# Gastroscopy-Controller_USB.net
KiCad netlist of a schematic drawn in Altium Designer
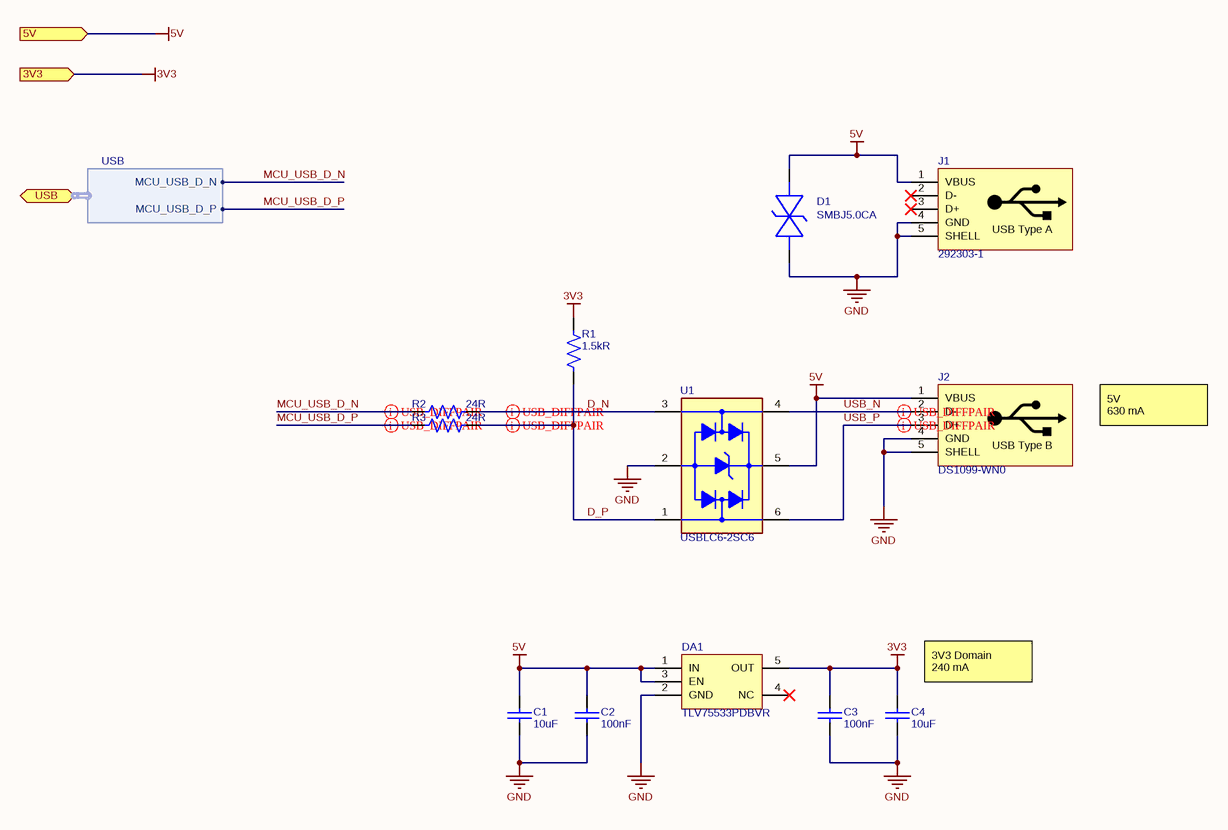
[diagram p0: Gastroscopy-Controller_USB.SchDoc]

(export (version "E")
  (design (tool "Eeschema 10.0.6"))
  (components
    (comp (ref "C1")
      (value "10uF")
      (footprint "CAP_0805")
      (description "CAP CER 10UF 16V X7R 0805")
      (fields (field (name "TOLERANCE") "10%") (field (name "VOLTAGE") "16V"))
      (libsource (lib "Gastroscopy-Controller") (part "CL21B106KOQNNNE"))
    )
    (comp (ref "C2")
      (value "100nF")
      (footprint "CAP_0603")
      (description "CAP CER 0.1UF 50V X7R 0603")
      (fields (field (name "TOLERANCE") "10%"))
      (libsource (lib "Gastroscopy-Controller") (part "CL10B104KB8NNNL"))
    )
    (comp (ref "C3")
      (value "100nF")
      (footprint "CAP_0603")
      (description "CAP CER 0.1UF 50V X7R 0603")
      (fields (field (name "TOLERANCE") "10%"))
      (libsource (lib "Gastroscopy-Controller") (part "CL10B104KB8NNNL"))
    )
    (comp (ref "C4")
      (value "10uF")
      (footprint "CAP_0805")
      (description "CAP CER 10UF 16V X7R 0805")
      (fields (field (name "TOLERANCE") "10%") (field (name "VOLTAGE") "16V"))
      (libsource (lib "Gastroscopy-Controller") (part "CL21B106KOQNNNE"))
    )
    (comp (ref "D1")
      (value "SMBJ5.0CA")
      (footprint "SMB-BIDIR")
      (description "TVS DIODE 5VWM 9.2VC SMB")
      (libsource (lib "Gastroscopy-Controller") (part "SMBJ5.0CA"))
    )
    (comp (ref "DA1")
      (value "TLV75533PDBVR")
      (footprint "SOT-23-5")
      (description "IC REG LINEAR 3.3V 500MA SOT23-5")
      (libsource (lib "Gastroscopy-Controller") (part "TLV75533PDBVR"))
    )
    (comp (ref "J1")
      (value "292303-1")
      (footprint "292303-1")
      (description "Conn USB 2.0 Type A RCP 4 POS 2mm/2.5mm Solder RA Thru-Hole 4 Terminal 1 Port Box/Tube")
      (libsource (lib "Gastroscopy-Controller") (part "292303-1"))
    )
    (comp (ref "J2")
      (value "DS1099-WN0")
      (footprint "DS1099-WN0")
      (description "CONN TYPE B SKT HORIZONTAL TH")
      (libsource (lib "Industrial-Controller") (part "DS1099-WN0"))
    )
    (comp (ref "R1")
      (value "1.5kR")
      (footprint "RES_0603")
      (description "RES 1.5K OHM 1% 1/10W 0603")
      (fields (field (name "TOLERANCE") "1%"))
      (libsource (lib "Gastroscopy-Controller") (part "RC0603FR-071K5L"))
    )
    (comp (ref "R2")
      (value "24R")
      (footprint "RES_0603")
      (description "RES 24 OHM 1% 1/10W 0603")
      (fields (field (name "TOLERANCE") "1%"))
      (libsource (lib "Gastroscopy-Controller") (part "RC0603FR-0724RL"))
    )
    (comp (ref "R3")
      (value "24R")
      (footprint "RES_0603")
      (description "RES 24 OHM 1% 1/10W 0603")
      (fields (field (name "TOLERANCE") "1%"))
      (libsource (lib "Gastroscopy-Controller") (part "RC0603FR-0724RL"))
    )
    (comp (ref "U1")
      (value "USBLC6-2SC6")
      (footprint "SOT-23-6")
      (description "TVS DIODE 5.25VWM 17VC SOT23-6")
      (libsource (lib "Industrial-Controller") (part "USBLC6-2SC6"))
    )
  )
  (nets
    (net (code "2") (name "/D_N") (class "Default")
      (node (ref "R2") (pin "2") (pinfunction "2_2") (pintype "passive"))
      (node (ref "U1") (pin "3") (pinfunction "I/O_2_3") (pintype "passive"))
    )
    (net (code "3") (name "/D_P") (class "Default")
      (node (ref "R1") (pin "2") (pinfunction "2_2") (pintype "passive"))
      (node (ref "R3") (pin "2") (pinfunction "2_2") (pintype "passive"))
      (node (ref "U1") (pin "1") (pinfunction "I/O_1_1") (pintype "passive"))
    )
    (net (code "4") (name "/MCU_USB_D_N") (class "Default")
      (node (ref "R2") (pin "1") (pinfunction "1_1") (pintype "passive"))
    )
    (net (code "5") (name "/MCU_USB_D_P") (class "Default")
      (node (ref "R3") (pin "1") (pinfunction "1_1") (pintype "passive"))
    )
    (net (code "6") (name "/USB_N") (class "Default")
      (node (ref "J2") (pin "2") (pinfunction "D-_2") (pintype "passive"))
      (node (ref "U1") (pin "4") (pinfunction "I/O_3_4") (pintype "passive"))
    )
    (net (code "7") (name "/USB_P") (class "Default")
      (node (ref "J2") (pin "3") (pinfunction "D+_3") (pintype "passive"))
      (node (ref "U1") (pin "6") (pinfunction "I/O_4_6") (pintype "passive"))
    )
    (net (code "9") (name "3V3") (class "Default")
      (node (ref "C3") (pin "1") (pinfunction "1_1") (pintype "passive"))
      (node (ref "C4") (pin "2") (pinfunction "2_2") (pintype "passive"))
      (node (ref "DA1") (pin "5") (pinfunction "OUT_5") (pintype "passive"))
      (node (ref "R1") (pin "1") (pinfunction "1_1") (pintype "passive"))
    )
    (net (code "10") (name "5V") (class "Default")
      (node (ref "C1") (pin "2") (pinfunction "2_2") (pintype "passive"))
      (node (ref "C2") (pin "1") (pinfunction "1_1") (pintype "passive"))
      (node (ref "D1") (pin "1") (pinfunction "1_1") (pintype "passive"))
      (node (ref "DA1") (pin "1") (pinfunction "IN_1") (pintype "passive"))
      (node (ref "DA1") (pin "3") (pinfunction "EN_3") (pintype "passive"))
      (node (ref "J1") (pin "1") (pinfunction "VBUS_1") (pintype "passive"))
      (node (ref "J2") (pin "1") (pinfunction "VBUS_1") (pintype "passive"))
      (node (ref "U1") (pin "5") (pinfunction "VBUS_5") (pintype "passive"))
    )
    (net (code "11") (name "GND") (class "Default")
      (node (ref "C1") (pin "1") (pinfunction "1_1") (pintype "passive"))
      (node (ref "C2") (pin "2") (pinfunction "2_2") (pintype "passive"))
      (node (ref "C3") (pin "2") (pinfunction "2_2") (pintype "passive"))
      (node (ref "C4") (pin "1") (pinfunction "1_1") (pintype "passive"))
      (node (ref "D1") (pin "2") (pinfunction "2_2") (pintype "passive"))
      (node (ref "DA1") (pin "2") (pinfunction "GND_2") (pintype "power_in"))
      (node (ref "J1") (pin "4") (pinfunction "GND_4") (pintype "passive"))
      (node (ref "J1") (pin "5") (pinfunction "SHELL_5") (pintype "passive"))
      (node (ref "J2") (pin "4") (pinfunction "GND_4") (pintype "passive"))
      (node (ref "J2") (pin "5") (pinfunction "SHELL_5") (pintype "passive"))
      (node (ref "U1") (pin "2") (pinfunction "GND_2") (pintype "passive"))
    )
    (net (code "12") (name "unconnected-(DA1-NC-Pad4)") (class "Default")
      (node (ref "DA1") (pin "4") (pinfunction "NC_4") (pintype "power_in+no_connect"))
    )
    (net (code "13") (name "unconnected-(J1-D+-Pad3)") (class "Default")
      (node (ref "J1") (pin "3") (pinfunction "D+_3") (pintype "passive+no_connect"))
    )
    (net (code "14") (name "unconnected-(J1-D--Pad2)") (class "Default")
      (node (ref "J1") (pin "2") (pinfunction "D-_2") (pintype "passive+no_connect"))
    )
  )
)
